# MIXR_UI_-_Connectors.net
KiCad netlist of a schematic drawn in Altium Designer
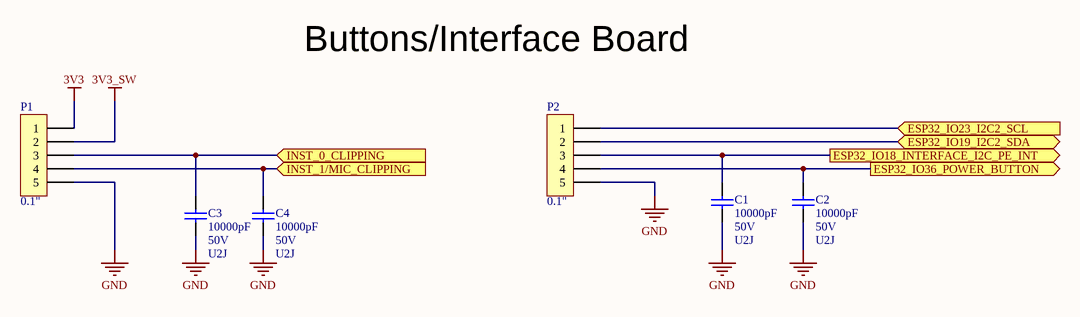
[diagram p0: MIXR UI - Connectors.SchDoc]

(export (version "E")
  (design (tool "Eeschema 10.0.6"))
  (components
    (comp (ref "C1")
      (value "CAP CER 10nF 50V 5% X7R 0603")
      (footprint "CAP, 0603")
      (description "10000pF ±5% 50V Ceramic Capacitor U2J 0603 (1608 Metric)")
      (fields
        (field (name "TOLERANCE") "±5%")
        (field (name "CAPACITANCE") "10000pF")
        (field (name "VOLTAGE") "50V")
        (field (name "TEMPERATURE COEFFICIENT") "U2J")
      )
      (libsource (lib "Schematic Diagrams") (part "CAP CER 10nF 50V 5% X7R 0603"))
    )
    (comp (ref "C2")
      (value "CAP CER 10nF 50V 5% X7R 0603")
      (footprint "CAP, 0603")
      (description "10000pF ±5% 50V Ceramic Capacitor U2J 0603 (1608 Metric)")
      (fields
        (field (name "TOLERANCE") "±5%")
        (field (name "CAPACITANCE") "10000pF")
        (field (name "VOLTAGE") "50V")
        (field (name "TEMPERATURE COEFFICIENT") "U2J")
      )
      (libsource (lib "Schematic Diagrams") (part "CAP CER 10nF 50V 5% X7R 0603"))
    )
    (comp (ref "C3")
      (value "CAP CER 10nF 50V 5% X7R 0603")
      (footprint "CAP, 0603")
      (description "10000pF ±5% 50V Ceramic Capacitor U2J 0603 (1608 Metric)")
      (fields
        (field (name "TOLERANCE") "±5%")
        (field (name "CAPACITANCE") "10000pF")
        (field (name "VOLTAGE") "50V")
        (field (name "TEMPERATURE COEFFICIENT") "U2J")
      )
      (libsource (lib "Schematic Diagrams") (part "CAP CER 10nF 50V 5% X7R 0603"))
    )
    (comp (ref "C4")
      (value "CAP CER 10nF 50V 5% X7R 0603")
      (footprint "CAP, 0603")
      (description "10000pF ±5% 50V Ceramic Capacitor U2J 0603 (1608 Metric)")
      (fields
        (field (name "TOLERANCE") "±5%")
        (field (name "CAPACITANCE") "10000pF")
        (field (name "VOLTAGE") "50V")
        (field (name "TEMPERATURE COEFFICIENT") "U2J")
      )
      (libsource (lib "Schematic Diagrams") (part "CAP CER 10nF 50V 5% X7R 0603"))
    )
    (comp (ref "P1")
      (value "0.1\"")
      (footprint "CONN, 5POS 0.3\" 0.100\" FEMALE HEADER")
      (description "5 Position Receptacle Connector Through Hole")
      (fields
        (field (name "MANUFACTURER") "Samtec")
        (field (name "MANUFACTURER PART NUMBER") "SSW-105-01-T-S")
      )
      (libsource (lib "Schematic Diagrams") (part "CONN 5POS 0.1{dblquote} 0.3{dblquote} FEMALE HEADER"))
    )
    (comp (ref "P2")
      (value "0.1\"")
      (footprint "CONN, 5POS 0.3\" 0.100\" FEMALE HEADER")
      (description "5 Position Receptacle Connector Through Hole")
      (fields
        (field (name "MANUFACTURER") "Samtec")
        (field (name "MANUFACTURER PART NUMBER") "SSW-105-01-T-S")
      )
      (libsource (lib "Schematic Diagrams") (part "CONN 5POS 0.1{dblquote} 0.3{dblquote} FEMALE HEADER"))
    )
  )
  (nets
    (net (code "1") (name "/ESP32_IO18_INTERFACE_I2C_PE_INT") (class "Default")
      (node (ref "C1") (pin "1") (pinfunction "1_1") (pintype "passive"))
      (node (ref "P2") (pin "3") (pinfunction "3_3") (pintype "passive"))
    )
    (net (code "2") (name "/ESP32_IO19_I2C2_SDA") (class "Default")
      (node (ref "P2") (pin "2") (pinfunction "2_2") (pintype "passive"))
    )
    (net (code "3") (name "/ESP32_IO23_I2C2_SCL") (class "Default")
      (node (ref "P2") (pin "1") (pinfunction "1_1") (pintype "passive"))
    )
    (net (code "4") (name "/ESP32_IO36_POWER_BUTTON") (class "Default")
      (node (ref "C2") (pin "1") (pinfunction "1_1") (pintype "passive"))
      (node (ref "P2") (pin "4") (pinfunction "4_4") (pintype "passive"))
    )
    (net (code "5") (name "/INST_0_CLIPPING") (class "Default")
      (node (ref "C3") (pin "1") (pinfunction "1_1") (pintype "passive"))
      (node (ref "P1") (pin "3") (pinfunction "3_3") (pintype "passive"))
    )
    (net (code "6") (name "/INST_1{slash}MIC_CLIPPING") (class "Default")
      (node (ref "C4") (pin "1") (pinfunction "1_1") (pintype "passive"))
      (node (ref "P1") (pin "4") (pinfunction "4_4") (pintype "passive"))
    )
    (net (code "7") (name "3V3") (class "Default")
      (node (ref "P1") (pin "1") (pinfunction "1_1") (pintype "passive"))
    )
    (net (code "8") (name "3V3_SW") (class "Default")
      (node (ref "P1") (pin "2") (pinfunction "2_2") (pintype "passive"))
    )
    (net (code "9") (name "GND") (class "Default")
      (node (ref "C1") (pin "2") (pinfunction "2_2") (pintype "passive"))
      (node (ref "C2") (pin "2") (pinfunction "2_2") (pintype "passive"))
      (node (ref "C3") (pin "2") (pinfunction "2_2") (pintype "passive"))
      (node (ref "C4") (pin "2") (pinfunction "2_2") (pintype "passive"))
      (node (ref "P1") (pin "5") (pinfunction "5_5") (pintype "passive"))
      (node (ref "P2") (pin "5") (pinfunction "5_5") (pintype "passive"))
    )
  )
)
